# imu.net
KiCad netlist of a schematic drawn in EAGLE
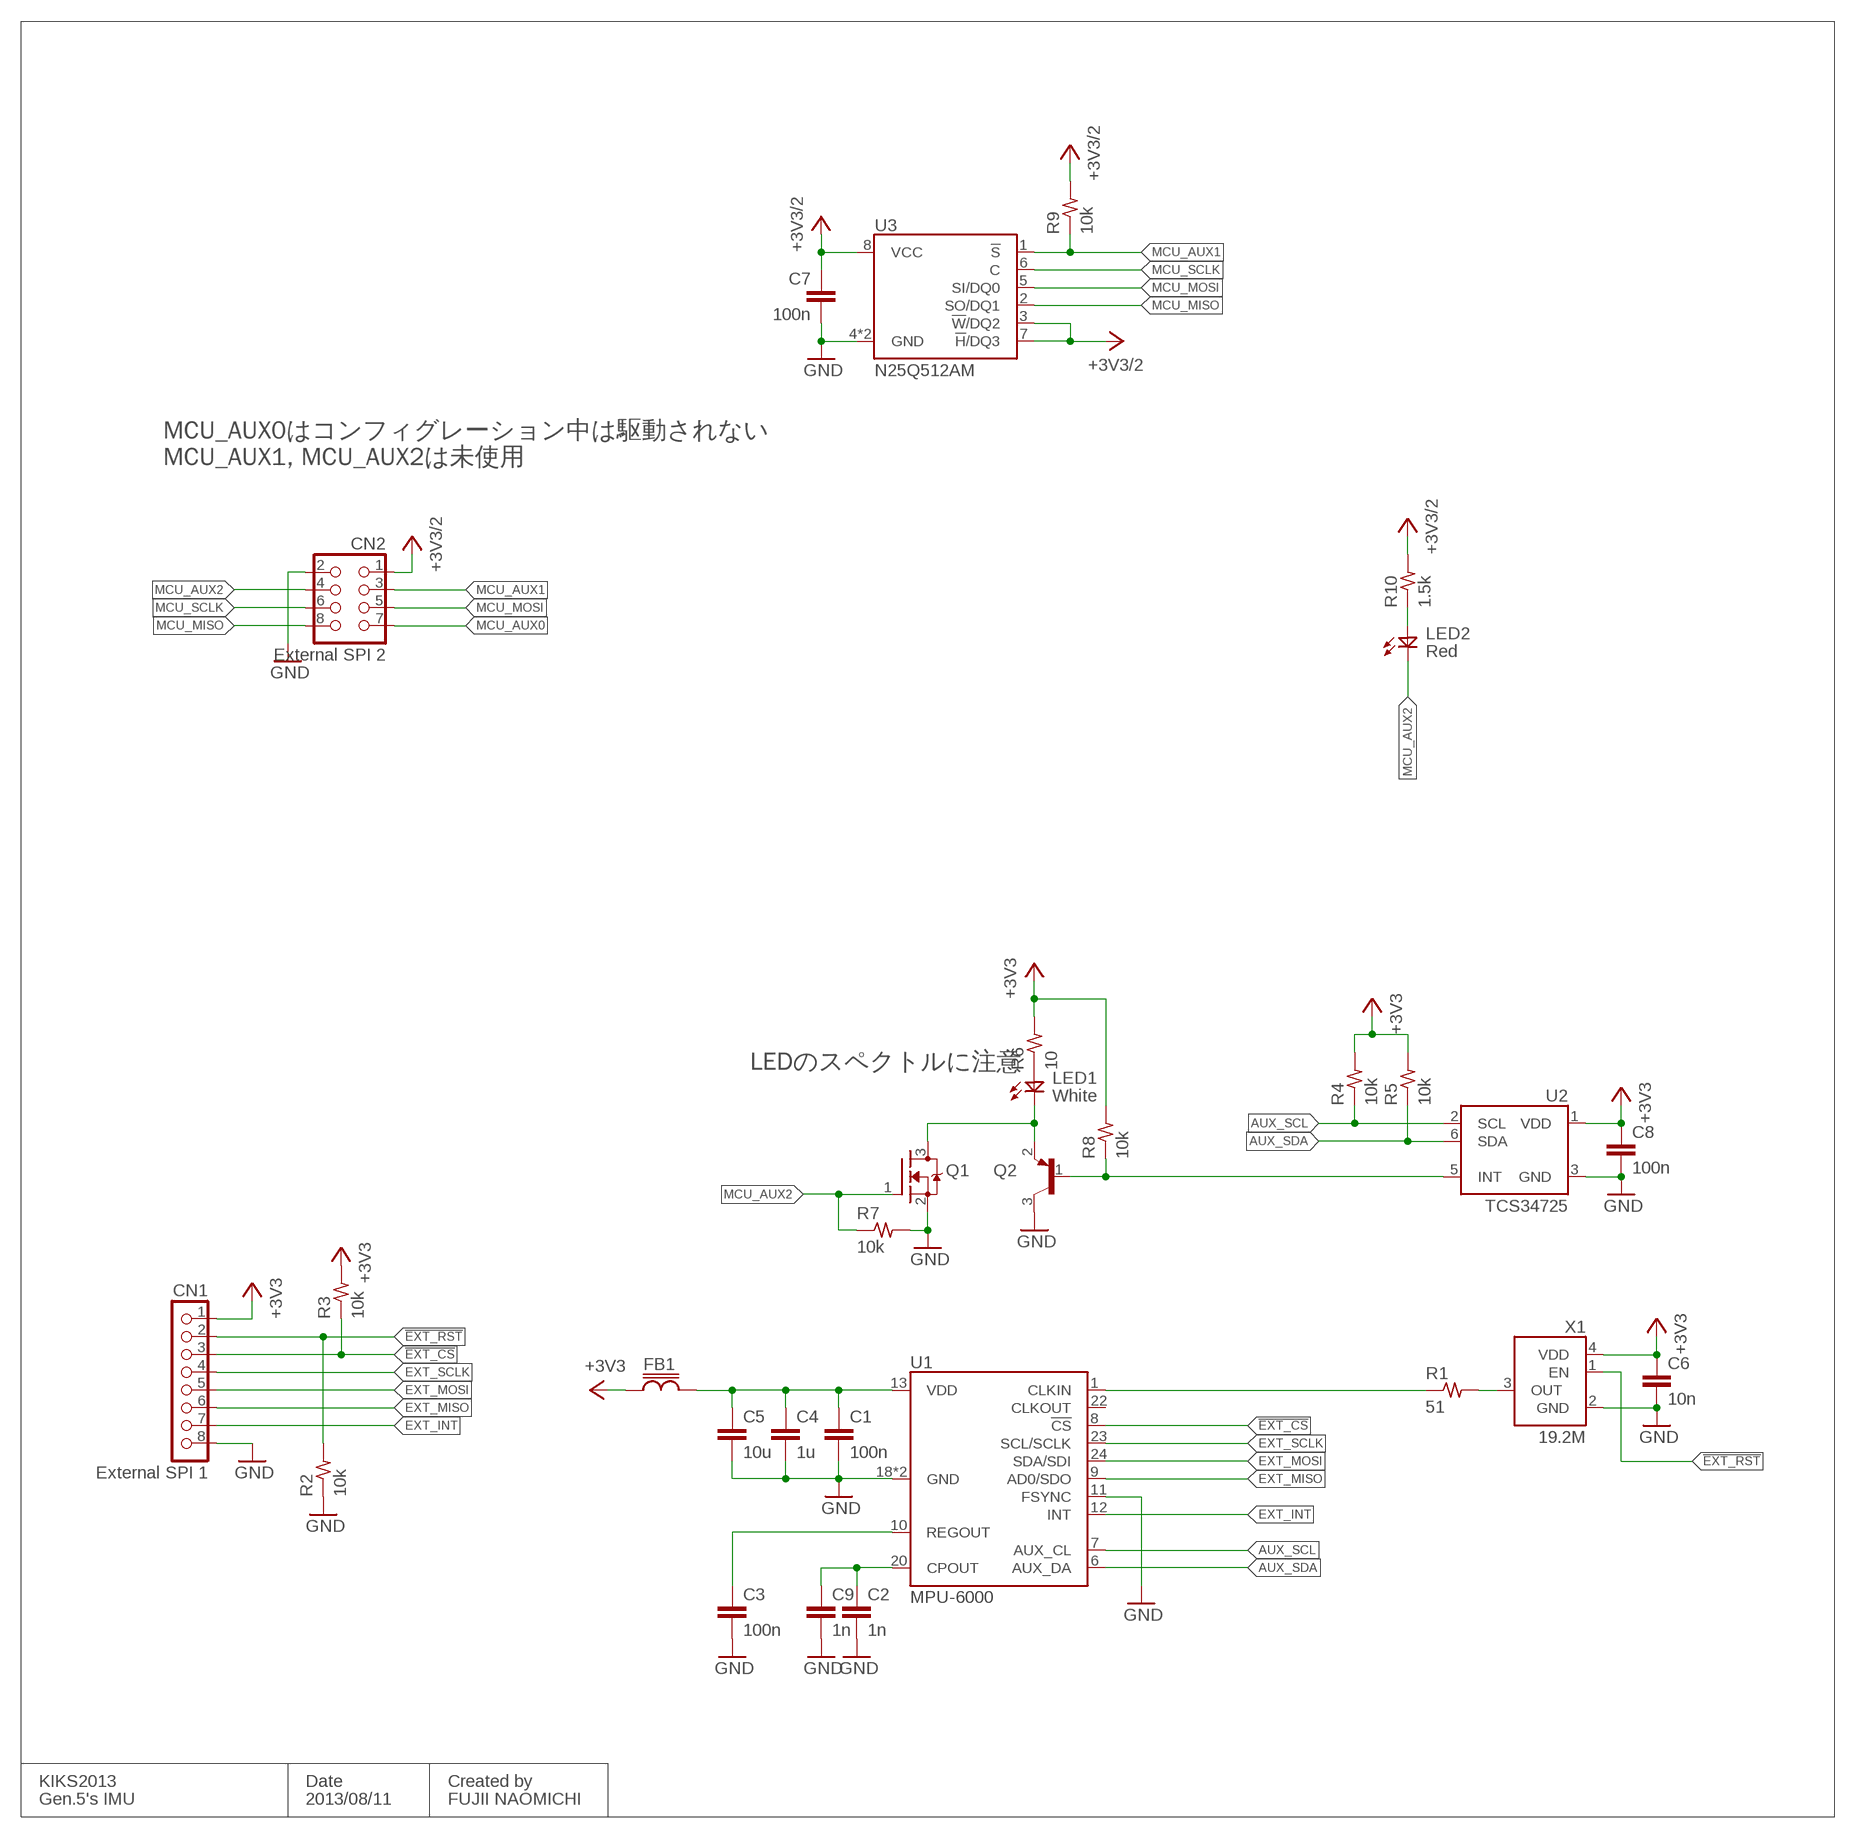
[diagram p0: schematic, sheet 1]

(export (version "E")
  (design (tool "Eeschema 10.0.6"))
  (components
    (comp (ref "C1")
      (value "100n")
      (footprint "eagle-import:1005")
      (libsource (lib "eagle-import") (part "C1005"))
    )
    (comp (ref "C2")
      (value "1n")
      (footprint "eagle-import:1005")
      (libsource (lib "eagle-import") (part "C1005"))
    )
    (comp (ref "C3")
      (value "100n")
      (footprint "eagle-import:1005")
      (libsource (lib "eagle-import") (part "C1005"))
    )
    (comp (ref "C4")
      (value "1u")
      (footprint "eagle-import:1005")
      (libsource (lib "eagle-import") (part "C1005"))
    )
    (comp (ref "C5")
      (value "10u")
      (footprint "eagle-import:1005")
      (libsource (lib "eagle-import") (part "C1005"))
    )
    (comp (ref "C6")
      (value "10n")
      (footprint "eagle-import:1005")
      (libsource (lib "eagle-import") (part "C1005"))
    )
    (comp (ref "C7")
      (value "100n")
      (footprint "eagle-import:1005")
      (libsource (lib "eagle-import") (part "C1005"))
    )
    (comp (ref "C8")
      (value "100n")
      (footprint "eagle-import:1005")
      (libsource (lib "eagle-import") (part "C1005"))
    )
    (comp (ref "C9")
      (value "1n")
      (footprint "eagle-import:1005")
      (libsource (lib "eagle-import") (part "C1005"))
    )
    (comp (ref "CN1")
      (value "External SPI 1")
      (footprint "eagle-import:PIN1X8")
      (libsource (lib "eagle-import") (part "PIN1X8"))
    )
    (comp (ref "CN2")
      (value "External SPI 2")
      (footprint "eagle-import:PIN2X4")
      (libsource (lib "eagle-import") (part "PIN2X4"))
    )
    (comp (ref "FB1")
      (value "FB1608")
      (footprint "eagle-import:1608")
      (libsource (lib "eagle-import") (part "FB1608"))
    )
    (comp (ref "LED1")
      (value "White")
      (footprint "eagle-import:1608")
      (libsource (lib "eagle-import") (part "LED1608"))
    )
    (comp (ref "LED2")
      (value "Red")
      (footprint "eagle-import:1608")
      (libsource (lib "eagle-import") (part "LED1608"))
    )
    (comp (ref "Q1")
      (value "MOS-N-SOT23")
      (footprint "eagle-import:SOT23-3")
      (libsource (lib "eagle-import") (part "MOS-N-SOT23"))
    )
    (comp (ref "Q2")
      (value "PNP-SOT23")
      (footprint "eagle-import:SOT23-3")
      (libsource (lib "eagle-import") (part "PNP-SOT23"))
    )
    (comp (ref "R1")
      (value "51")
      (footprint "eagle-import:1005")
      (libsource (lib "eagle-import") (part "R1005"))
    )
    (comp (ref "R2")
      (value "10k")
      (footprint "eagle-import:1005")
      (libsource (lib "eagle-import") (part "R1005"))
    )
    (comp (ref "R3")
      (value "10k")
      (footprint "eagle-import:1005")
      (libsource (lib "eagle-import") (part "R1005"))
    )
    (comp (ref "R4")
      (value "10k")
      (footprint "eagle-import:1005")
      (libsource (lib "eagle-import") (part "R1005"))
    )
    (comp (ref "R5")
      (value "10k")
      (footprint "eagle-import:1005")
      (libsource (lib "eagle-import") (part "R1005"))
    )
    (comp (ref "R6")
      (value "10")
      (footprint "eagle-import:1608")
      (libsource (lib "eagle-import") (part "R1608"))
    )
    (comp (ref "R7")
      (value "10k")
      (footprint "eagle-import:1005")
      (libsource (lib "eagle-import") (part "R1005"))
    )
    (comp (ref "R8")
      (value "10k")
      (footprint "eagle-import:1005")
      (libsource (lib "eagle-import") (part "R1005"))
    )
    (comp (ref "R9")
      (value "10k")
      (footprint "eagle-import:1005")
      (libsource (lib "eagle-import") (part "R1005"))
    )
    (comp (ref "R10")
      (value "1.5k")
      (footprint "eagle-import:1005")
      (libsource (lib "eagle-import") (part "R1005"))
    )
    (comp (ref "U1")
      (value "MPU-6000")
      (footprint "eagle-import:QFN24-0.5")
      (libsource (lib "eagle-import") (part "MPU-6000"))
    )
    (comp (ref "U2")
      (value "TCS34725")
      (footprint "eagle-import:FN-6")
      (libsource (lib "eagle-import") (part "TCS34725"))
    )
    (comp (ref "U3")
      (value "N25Q512AM")
      (footprint "eagle-import:DFN8-1.27")
      (libsource (lib "eagle-import") (part "N25Q512AM"))
    )
    (comp (ref "X1")
      (value "19.2M")
      (footprint "eagle-import:OSC2520")
      (libsource (lib "eagle-import") (part "ASDMB"))
    )
  )
  (nets
    (net (code "1") (name "+3V3") (class "Default")
      (node (ref "C6") (pin "1") (pinfunction "1_1") (pintype "passive"))
      (node (ref "C8") (pin "1") (pinfunction "1_1") (pintype "passive"))
      (node (ref "CN1") (pin "1") (pinfunction "1_1") (pintype "passive"))
      (node (ref "FB1") (pin "1") (pinfunction "1_1") (pintype "passive"))
      (node (ref "R3") (pin "2") (pinfunction "2_2") (pintype "passive"))
      (node (ref "R4") (pin "2") (pinfunction "2_2") (pintype "passive"))
      (node (ref "R5") (pin "2") (pinfunction "2_2") (pintype "passive"))
      (node (ref "R6") (pin "2") (pinfunction "2_2") (pintype "passive"))
      (node (ref "R8") (pin "2") (pinfunction "2_2") (pintype "passive"))
      (node (ref "U2") (pin "1") (pinfunction "VDD_1") (pintype "bidirectional"))
      (node (ref "X1") (pin "4") (pinfunction "VDD_4") (pintype "bidirectional"))
    )
    (net (code "2") (name "+3V3{slash}2") (class "Default")
      (node (ref "C7") (pin "1") (pinfunction "1_1") (pintype "passive"))
      (node (ref "CN2") (pin "1") (pinfunction "1_1") (pintype "passive"))
      (node (ref "R10") (pin "2") (pinfunction "2_2") (pintype "passive"))
      (node (ref "R9") (pin "2") (pinfunction "2_2") (pintype "passive"))
      (node (ref "U3") (pin "3") (pinfunction "~{W}/DQ2_3") (pintype "bidirectional"))
      (node (ref "U3") (pin "7") (pinfunction "~{H}/DQ3_7") (pintype "bidirectional"))
      (node (ref "U3") (pin "8") (pinfunction "VCC_8") (pintype "bidirectional"))
    )
    (net (code "3") (name "/~{EXT_CS}") (class "Default")
      (node (ref "CN1") (pin "3") (pinfunction "3_3") (pintype "passive"))
      (node (ref "R3") (pin "1") (pinfunction "1_1") (pintype "passive"))
      (node (ref "U1") (pin "8") (pinfunction "~{CS}_8") (pintype "bidirectional"))
    )
    (net (code "4") (name "/~{EXT_RST}") (class "Default")
      (node (ref "CN1") (pin "2") (pinfunction "2_2") (pintype "passive"))
      (node (ref "R2") (pin "2") (pinfunction "2_2") (pintype "passive"))
      (node (ref "X1") (pin "1") (pinfunction "EN_1") (pintype "bidirectional"))
    )
    (net (code "5") (name "AUX_SCL") (class "Default")
      (node (ref "R4") (pin "1") (pinfunction "1_1") (pintype "passive"))
      (node (ref "U1") (pin "7") (pinfunction "AUX_CL_7") (pintype "bidirectional"))
      (node (ref "U2") (pin "2") (pinfunction "SCL_2") (pintype "bidirectional"))
    )
    (net (code "6") (name "AUX_SDA") (class "Default")
      (node (ref "R5") (pin "1") (pinfunction "1_1") (pintype "passive"))
      (node (ref "U1") (pin "6") (pinfunction "AUX_DA_6") (pintype "bidirectional"))
      (node (ref "U2") (pin "6") (pinfunction "SDA_6") (pintype "bidirectional"))
    )
    (net (code "7") (name "EXT_INT") (class "Default")
      (node (ref "CN1") (pin "7") (pinfunction "7_7") (pintype "passive"))
      (node (ref "U1") (pin "12") (pinfunction "INT_12") (pintype "bidirectional"))
    )
    (net (code "8") (name "EXT_MISO") (class "Default")
      (node (ref "CN1") (pin "6") (pinfunction "6_6") (pintype "passive"))
      (node (ref "U1") (pin "9") (pinfunction "AD0/SDO_9") (pintype "bidirectional"))
    )
    (net (code "9") (name "EXT_MOSI") (class "Default")
      (node (ref "CN1") (pin "5") (pinfunction "5_5") (pintype "passive"))
      (node (ref "U1") (pin "24") (pinfunction "SDA/SDI_24") (pintype "bidirectional"))
    )
    (net (code "10") (name "EXT_SCLK") (class "Default")
      (node (ref "CN1") (pin "4") (pinfunction "4_4") (pintype "passive"))
      (node (ref "U1") (pin "23") (pinfunction "SCL/SCLK_23") (pintype "bidirectional"))
    )
    (net (code "11") (name "GND") (class "Default")
      (node (ref "C1") (pin "2") (pinfunction "2_2") (pintype "passive"))
      (node (ref "C2") (pin "2") (pinfunction "2_2") (pintype "passive"))
      (node (ref "C3") (pin "2") (pinfunction "2_2") (pintype "passive"))
      (node (ref "C4") (pin "2") (pinfunction "2_2") (pintype "passive"))
      (node (ref "C5") (pin "2") (pinfunction "2_2") (pintype "passive"))
      (node (ref "C6") (pin "2") (pinfunction "2_2") (pintype "passive"))
      (node (ref "C7") (pin "2") (pinfunction "2_2") (pintype "passive"))
      (node (ref "C8") (pin "2") (pinfunction "2_2") (pintype "passive"))
      (node (ref "C9") (pin "2") (pinfunction "2_2") (pintype "passive"))
      (node (ref "CN1") (pin "8") (pinfunction "8_8") (pintype "passive"))
      (node (ref "CN2") (pin "2") (pinfunction "2_2") (pintype "passive"))
      (node (ref "Q1") (pin "2") (pinfunction "S_2") (pintype "passive"))
      (node (ref "Q2") (pin "3") (pinfunction "C_3") (pintype "passive"))
      (node (ref "R2") (pin "1") (pinfunction "1_1") (pintype "passive"))
      (node (ref "R7") (pin "2") (pinfunction "2_2") (pintype "passive"))
      (node (ref "U1") (pin "11") (pinfunction "FSYNC_11") (pintype "bidirectional"))
      (node (ref "U1") (pin "18") (pinfunction "GND_18") (pintype "bidirectional"))
      (node (ref "U1") (pin "PAD") (pinfunction "GND_PAD") (pintype "bidirectional"))
      (node (ref "U2") (pin "3") (pinfunction "GND_3") (pintype "bidirectional"))
      (node (ref "U3") (pin "4") (pinfunction "GND_4") (pintype "bidirectional"))
      (node (ref "U3") (pin "PAD") (pinfunction "GND_PAD") (pintype "bidirectional"))
      (node (ref "X1") (pin "2") (pinfunction "GND_2") (pintype "bidirectional"))
    )
    (net (code "12") (name "MCU_AUX0") (class "Default")
      (node (ref "CN2") (pin "7") (pinfunction "7_7") (pintype "passive"))
    )
    (net (code "13") (name "MCU_AUX1") (class "Default")
      (node (ref "CN2") (pin "3") (pinfunction "3_3") (pintype "passive"))
      (node (ref "R9") (pin "1") (pinfunction "1_1") (pintype "passive"))
      (node (ref "U3") (pin "1") (pinfunction "~{S}_1") (pintype "bidirectional"))
    )
    (net (code "14") (name "MCU_AUX2") (class "Default")
      (node (ref "CN2") (pin "4") (pinfunction "4_4") (pintype "passive"))
      (node (ref "LED2") (pin "K") (pinfunction "K_K") (pintype "passive"))
      (node (ref "Q1") (pin "1") (pinfunction "G_1") (pintype "passive"))
      (node (ref "R7") (pin "1") (pinfunction "1_1") (pintype "passive"))
    )
    (net (code "15") (name "MCU_MISO") (class "Default")
      (node (ref "CN2") (pin "8") (pinfunction "8_8") (pintype "passive"))
      (node (ref "U3") (pin "2") (pinfunction "SO/DQ1_2") (pintype "bidirectional"))
    )
    (net (code "16") (name "MCU_MOSI") (class "Default")
      (node (ref "CN2") (pin "5") (pinfunction "5_5") (pintype "passive"))
      (node (ref "U3") (pin "5") (pinfunction "SI/DQ0_5") (pintype "bidirectional"))
    )
    (net (code "17") (name "MCU_SCLK") (class "Default")
      (node (ref "CN2") (pin "6") (pinfunction "6_6") (pintype "passive"))
      (node (ref "U3") (pin "6") (pinfunction "C_6") (pintype "bidirectional"))
    )
    (net (code "18") (name "Net-(LED1-PadA)") (class "Default")
      (node (ref "LED1") (pin "A") (pinfunction "A_A") (pintype "passive"))
      (node (ref "R6") (pin "1") (pinfunction "1_1") (pintype "passive"))
    )
    (net (code "19") (name "Net-(LED2-PadA)") (class "Default")
      (node (ref "LED2") (pin "A") (pinfunction "A_A") (pintype "passive"))
      (node (ref "R10") (pin "1") (pinfunction "1_1") (pintype "passive"))
    )
    (net (code "20") (name "Net-(Q1-D)") (class "Default")
      (node (ref "LED1") (pin "K") (pinfunction "K_K") (pintype "passive"))
      (node (ref "Q1") (pin "3") (pinfunction "D_3") (pintype "passive"))
      (node (ref "Q2") (pin "2") (pinfunction "E_2") (pintype "passive"))
    )
    (net (code "21") (name "Net-(Q2-B)") (class "Default")
      (node (ref "Q2") (pin "1") (pinfunction "B_1") (pintype "passive"))
      (node (ref "R8") (pin "1") (pinfunction "1_1") (pintype "passive"))
      (node (ref "U2") (pin "5") (pinfunction "INT_5") (pintype "bidirectional"))
    )
    (net (code "22") (name "Net-(U1-CLKIN)") (class "Default")
      (node (ref "R1") (pin "1") (pinfunction "1_1") (pintype "passive"))
      (node (ref "U1") (pin "1") (pinfunction "CLKIN_1") (pintype "bidirectional"))
    )
    (net (code "23") (name "Net-(U1-CPOUT)") (class "Default")
      (node (ref "C2") (pin "1") (pinfunction "1_1") (pintype "passive"))
      (node (ref "C9") (pin "1") (pinfunction "1_1") (pintype "passive"))
      (node (ref "U1") (pin "20") (pinfunction "CPOUT_20") (pintype "bidirectional"))
    )
    (net (code "24") (name "Net-(U1-REGOUT)") (class "Default")
      (node (ref "C3") (pin "1") (pinfunction "1_1") (pintype "passive"))
      (node (ref "U1") (pin "10") (pinfunction "REGOUT_10") (pintype "bidirectional"))
    )
    (net (code "25") (name "Net-(U1-VDD)") (class "Default")
      (node (ref "C1") (pin "1") (pinfunction "1_1") (pintype "passive"))
      (node (ref "C4") (pin "1") (pinfunction "1_1") (pintype "passive"))
      (node (ref "C5") (pin "1") (pinfunction "1_1") (pintype "passive"))
      (node (ref "FB1") (pin "2") (pinfunction "2_2") (pintype "passive"))
      (node (ref "U1") (pin "13") (pinfunction "VDD_13") (pintype "bidirectional"))
    )
    (net (code "26") (name "Net-(X1-OUT)") (class "Default")
      (node (ref "R1") (pin "2") (pinfunction "2_2") (pintype "passive"))
      (node (ref "X1") (pin "3") (pinfunction "OUT_3") (pintype "bidirectional"))
    )
    (net (code "27") (name "unconnected-(U1-CLKOUT-Pad22)") (class "Default")
      (node (ref "U1") (pin "22") (pinfunction "CLKOUT_22") (pintype "bidirectional"))
    )
  )
)
